# PIR_Motion_Sensor.net
KiCad netlist of a schematic drawn in Altium Designer
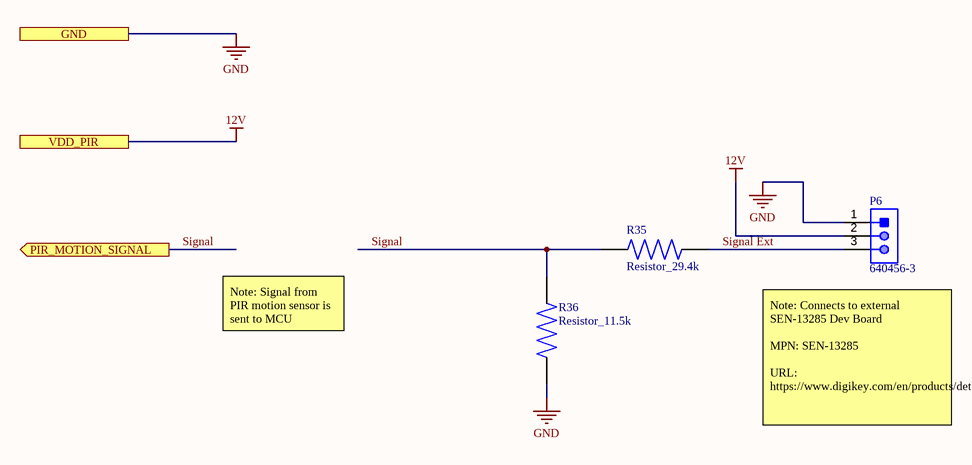
[diagram p0: PIR_Motion_Sensor.SchDoc]

(export (version "E")
  (design (tool "Eeschema 10.0.6"))
  (components
    (comp (ref "P6")
      (value "640456-3")
      (footprint "TECO-640456-3")
      (description "Male Header, Pitch 2.54 mm, 1 x 3 Position, Height 10.03 mm, Tail Length 3.56 mm, -55 to 105 degC")
      (fields (field (name "MANUFACTURER") "TE Connectivity"))
      (libsource (lib "Altium Content Vault") (part "CN-1P-M-R3"))
    )
    (comp (ref "R35")
      (value "Resistor_29.4k")
      (footprint "Resistor_29.4k")
      (description "Res Thick Film 0402 29.4K Ohm 1% 0.063W ±100ppm/°C Molded SMD Paper T/R")
      (fields
        (field (name "MANUFACTURER") "KOA Speer")
        (field (name "MANUFACTURER PART NUMBER") "RN73R2ATTD2942F50")
      )
      (libsource (lib "Schematic_Lib") (part "Resistor_29.4k"))
    )
    (comp (ref "R36")
      (value "Resistor_11.5k")
      (footprint "Resistor_11.5k")
      (description "Res 11.5K Ohm 0.5% 1/10W 0603")
      (fields
        (field (name "MANUFACTURER") "KOA Speer")
        (field (name "MANUFACTURER PART NUMBER") "RN73R1JTTD1152D100")
      )
      (libsource (lib "Schematic_Lib") (part "Resistor_11.5k"))
    )
  )
  (nets
    (net (code "1") (name "/Signal") (class "Default")
      (node (ref "R35") (pin "1") (pinfunction "1_1") (pintype "passive"))
      (node (ref "R36") (pin "2") (pinfunction "2_2") (pintype "passive"))
    )
    (net (code "2") (name "/Signal Ext") (class "Default")
      (node (ref "P6") (pin "3") (pinfunction "3_3") (pintype "passive"))
      (node (ref "R35") (pin "2") (pinfunction "2_2") (pintype "passive"))
    )
    (net (code "3") (name "12V") (class "Default")
      (node (ref "P6") (pin "2") (pinfunction "2_2") (pintype "passive"))
    )
    (net (code "4") (name "GND") (class "Default")
      (node (ref "P6") (pin "1") (pinfunction "1_1") (pintype "passive"))
      (node (ref "R36") (pin "1") (pinfunction "1_1") (pintype "passive"))
    )
  )
)
